# FlashPanelV6_0.net
KiCad netlist of a schematic drawn in EAGLE
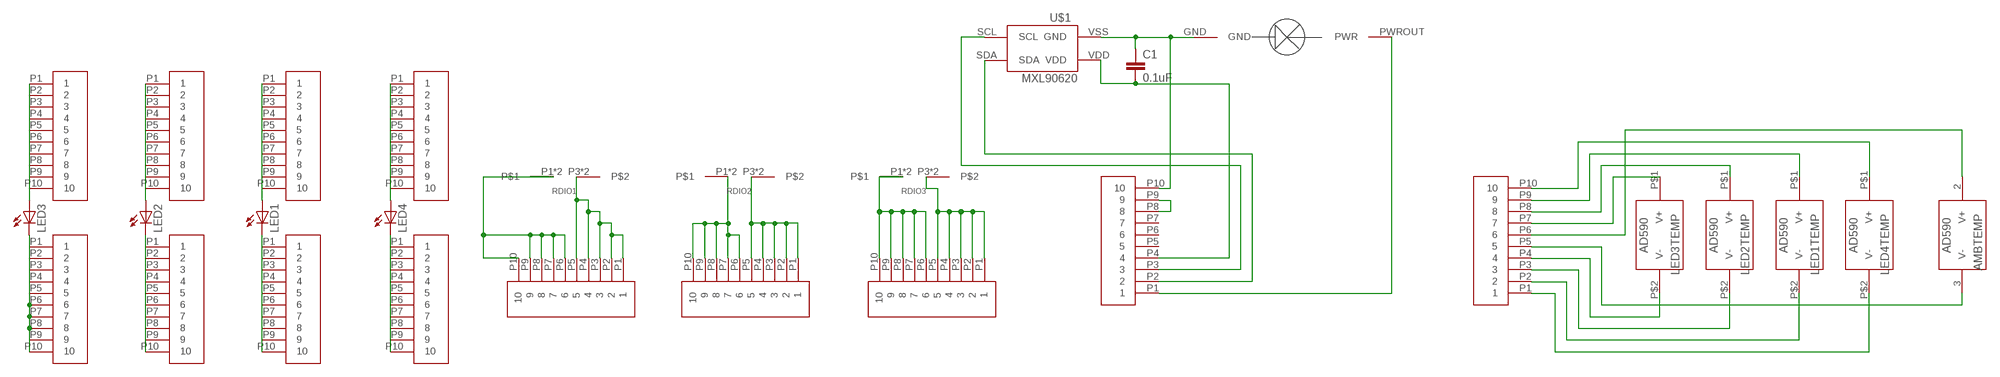
[diagram p0: schematic, sheet 1]

(export (version "E")
  (design (tool "Eeschema 10.0.6"))
  (components
    (comp (ref "AMBTEMP")
      (value "AD590")
      (footprint "eagle-import:8SOIC")
      (libsource (lib "eagle-import") (part "AD590-SOIC-8"))
    )
    (comp (ref "ANTDEP1M")
      (value "10PINMALE")
      (footprint "eagle-import:10PINMALE")
      (libsource (lib "eagle-import") (part "10PINMALE"))
    )
    (comp (ref "ANTDEP2M")
      (value "10PINMALE")
      (footprint "eagle-import:10PINMALE")
      (libsource (lib "eagle-import") (part "10PINMALE"))
    )
    (comp (ref "ANTDEP3M")
      (value "10PINMALE")
      (footprint "eagle-import:10PINMALE")
      (libsource (lib "eagle-import") (part "10PINMALE"))
    )
    (comp (ref "C1")
      (value "0.1uF")
      (footprint "eagle-import:0805")
      (libsource (lib "eagle-import") (part "CAP0805"))
    )
    (comp (ref "CONN13M")
      (value "10PINMALE")
      (footprint "eagle-import:10PINMALE")
      (libsource (lib "eagle-import") (part "10PINMALE"))
    )
    (comp (ref "LED1")
      (value "CXM27")
      (footprint "eagle-import:CXM27")
      (libsource (lib "eagle-import") (part "CXM27"))
    )
    (comp (ref "LED1+M")
      (value "10PINMALE")
      (footprint "eagle-import:10PINMALE")
      (libsource (lib "eagle-import") (part "10PINMALE"))
    )
    (comp (ref "LED1-M")
      (value "10PINMALE")
      (footprint "eagle-import:10PINMALE")
      (libsource (lib "eagle-import") (part "10PINMALE"))
    )
    (comp (ref "LED1TEMP")
      (value "AD590-TH")
      (footprint "eagle-import:AD590TH")
      (libsource (lib "eagle-import") (part "AD590-TH"))
    )
    (comp (ref "LED2")
      (value "CXM27")
      (footprint "eagle-import:CXM27")
      (libsource (lib "eagle-import") (part "CXM27"))
    )
    (comp (ref "LED2+M")
      (value "10PINMALE")
      (footprint "eagle-import:10PINMALE")
      (libsource (lib "eagle-import") (part "10PINMALE"))
    )
    (comp (ref "LED2-M")
      (value "10PINMALE")
      (footprint "eagle-import:10PINMALE")
      (libsource (lib "eagle-import") (part "10PINMALE"))
    )
    (comp (ref "LED2TEMP")
      (value "AD590-TH")
      (footprint "eagle-import:AD590TH")
      (libsource (lib "eagle-import") (part "AD590-TH"))
    )
    (comp (ref "LED3")
      (value "CXM27")
      (footprint "eagle-import:CXM27")
      (libsource (lib "eagle-import") (part "CXM27"))
    )
    (comp (ref "LED3+M")
      (value "10PINMALE")
      (footprint "eagle-import:10PINMALE")
      (libsource (lib "eagle-import") (part "10PINMALE"))
    )
    (comp (ref "LED3-M")
      (value "10PINMALE")
      (footprint "eagle-import:10PINMALE")
      (libsource (lib "eagle-import") (part "10PINMALE"))
    )
    (comp (ref "LED3TEMP")
      (value "AD590-TH")
      (footprint "eagle-import:AD590TH")
      (libsource (lib "eagle-import") (part "AD590-TH"))
    )
    (comp (ref "LED4")
      (value "CXM27")
      (footprint "eagle-import:CXM27")
      (libsource (lib "eagle-import") (part "CXM27"))
    )
    (comp (ref "LED4+M")
      (value "10PINMALE")
      (footprint "eagle-import:10PINMALE")
      (libsource (lib "eagle-import") (part "10PINMALE"))
    )
    (comp (ref "LED4-M")
      (value "10PINMALE")
      (footprint "eagle-import:10PINMALE")
      (libsource (lib "eagle-import") (part "10PINMALE"))
    )
    (comp (ref "LED4TEMP")
      (value "AD590-TH")
      (footprint "eagle-import:AD590TH")
      (libsource (lib "eagle-import") (part "AD590-TH"))
    )
    (comp (ref "RDIO1")
      (value "RDIO")
      (footprint "eagle-import:RDIO_DPLY")
      (libsource (lib "eagle-import") (part "RDIO"))
    )
    (comp (ref "RDIO2")
      (value "RDIO")
      (footprint "eagle-import:RDIO_DPLY")
      (libsource (lib "eagle-import") (part "RDIO"))
    )
    (comp (ref "RDIO3")
      (value "RDIO")
      (footprint "eagle-import:RDIO_DPLY")
      (libsource (lib "eagle-import") (part "RDIO"))
    )
    (comp (ref "TEMPCONNM")
      (value "10PINMALE")
      (footprint "eagle-import:10PINMALE")
      (libsource (lib "eagle-import") (part "10PINMALE"))
    )
    (comp (ref "U$1")
      (value "MXL90620")
      (footprint "eagle-import:MXL90620")
      (libsource (lib "eagle-import") (part "MXL90620"))
    )
    (comp (ref "U$2")
      (value "PHOTODETECTBOTTOM")
      (footprint "eagle-import:PHOTODETECTBOTTOM")
      (libsource (lib "eagle-import") (part "PHOTODETECTBOTTOM"))
    )
  )
  (nets
    (net (code "1") (name "Net-(AMBTEMP-V+)") (class "Default")
      (node (ref "AMBTEMP") (pin "2") (pinfunction "V+_2") (pintype "bidirectional"))
      (node (ref "TEMPCONNM") (pin "P6") (pinfunction "6_P6") (pintype "bidirectional"))
    )
    (net (code "2") (name "Net-(AMBTEMP-V-)") (class "Default")
      (node (ref "AMBTEMP") (pin "3") (pinfunction "V-_3") (pintype "bidirectional"))
      (node (ref "TEMPCONNM") (pin "P5") (pinfunction "5_P5") (pintype "bidirectional"))
    )
    (net (code "3") (name "Net-(ANTDEP1M-1)") (class "Default")
      (node (ref "ANTDEP1M") (pin "P1") (pinfunction "1_P1") (pintype "bidirectional"))
      (node (ref "ANTDEP1M") (pin "P2") (pinfunction "2_P2") (pintype "bidirectional"))
      (node (ref "ANTDEP1M") (pin "P3") (pinfunction "3_P3") (pintype "bidirectional"))
      (node (ref "ANTDEP1M") (pin "P4") (pinfunction "4_P4") (pintype "bidirectional"))
      (node (ref "ANTDEP1M") (pin "P5") (pinfunction "5_P5") (pintype "bidirectional"))
      (node (ref "RDIO1") (pin "P3") (pinfunction "P$2_P3") (pintype "bidirectional"))
      (node (ref "RDIO1") (pin "P4") (pinfunction "P$2_P4") (pintype "bidirectional"))
    )
    (net (code "4") (name "Net-(ANTDEP1M-10)") (class "Default")
      (node (ref "ANTDEP1M") (pin "P10") (pinfunction "10_P10") (pintype "bidirectional"))
      (node (ref "ANTDEP1M") (pin "P6") (pinfunction "6_P6") (pintype "bidirectional"))
      (node (ref "ANTDEP1M") (pin "P7") (pinfunction "7_P7") (pintype "bidirectional"))
      (node (ref "ANTDEP1M") (pin "P8") (pinfunction "8_P8") (pintype "bidirectional"))
      (node (ref "ANTDEP1M") (pin "P9") (pinfunction "9_P9") (pintype "bidirectional"))
      (node (ref "RDIO1") (pin "P1") (pinfunction "P$1_P1") (pintype "bidirectional"))
      (node (ref "RDIO1") (pin "P2") (pinfunction "P$1_P2") (pintype "bidirectional"))
    )
    (net (code "5") (name "Net-(ANTDEP2M-1)") (class "Default")
      (node (ref "ANTDEP2M") (pin "P1") (pinfunction "1_P1") (pintype "bidirectional"))
      (node (ref "ANTDEP2M") (pin "P2") (pinfunction "2_P2") (pintype "bidirectional"))
      (node (ref "ANTDEP2M") (pin "P3") (pinfunction "3_P3") (pintype "bidirectional"))
      (node (ref "ANTDEP2M") (pin "P4") (pinfunction "4_P4") (pintype "bidirectional"))
      (node (ref "ANTDEP2M") (pin "P5") (pinfunction "5_P5") (pintype "bidirectional"))
      (node (ref "RDIO2") (pin "P3") (pinfunction "P$2_P3") (pintype "bidirectional"))
      (node (ref "RDIO2") (pin "P4") (pinfunction "P$2_P4") (pintype "bidirectional"))
    )
    (net (code "6") (name "Net-(ANTDEP2M-10)") (class "Default")
      (node (ref "ANTDEP2M") (pin "P10") (pinfunction "10_P10") (pintype "bidirectional"))
      (node (ref "ANTDEP2M") (pin "P6") (pinfunction "6_P6") (pintype "bidirectional"))
      (node (ref "ANTDEP2M") (pin "P7") (pinfunction "7_P7") (pintype "bidirectional"))
      (node (ref "ANTDEP2M") (pin "P8") (pinfunction "8_P8") (pintype "bidirectional"))
      (node (ref "ANTDEP2M") (pin "P9") (pinfunction "9_P9") (pintype "bidirectional"))
      (node (ref "RDIO2") (pin "P1") (pinfunction "P$1_P1") (pintype "bidirectional"))
      (node (ref "RDIO2") (pin "P2") (pinfunction "P$1_P2") (pintype "bidirectional"))
    )
    (net (code "7") (name "Net-(ANTDEP3M-1)") (class "Default")
      (node (ref "ANTDEP3M") (pin "P1") (pinfunction "1_P1") (pintype "bidirectional"))
      (node (ref "ANTDEP3M") (pin "P2") (pinfunction "2_P2") (pintype "bidirectional"))
      (node (ref "ANTDEP3M") (pin "P3") (pinfunction "3_P3") (pintype "bidirectional"))
      (node (ref "ANTDEP3M") (pin "P4") (pinfunction "4_P4") (pintype "bidirectional"))
      (node (ref "ANTDEP3M") (pin "P5") (pinfunction "5_P5") (pintype "bidirectional"))
      (node (ref "RDIO3") (pin "P3") (pinfunction "P$2_P3") (pintype "bidirectional"))
      (node (ref "RDIO3") (pin "P4") (pinfunction "P$2_P4") (pintype "bidirectional"))
    )
    (net (code "8") (name "Net-(ANTDEP3M-10)") (class "Default")
      (node (ref "ANTDEP3M") (pin "P10") (pinfunction "10_P10") (pintype "bidirectional"))
      (node (ref "ANTDEP3M") (pin "P6") (pinfunction "6_P6") (pintype "bidirectional"))
      (node (ref "ANTDEP3M") (pin "P7") (pinfunction "7_P7") (pintype "bidirectional"))
      (node (ref "ANTDEP3M") (pin "P8") (pinfunction "8_P8") (pintype "bidirectional"))
      (node (ref "ANTDEP3M") (pin "P9") (pinfunction "9_P9") (pintype "bidirectional"))
      (node (ref "RDIO3") (pin "P1") (pinfunction "P$1_P1") (pintype "bidirectional"))
      (node (ref "RDIO3") (pin "P2") (pinfunction "P$1_P2") (pintype "bidirectional"))
    )
    (net (code "9") (name "Net-(CONN13M-1)") (class "Default")
      (node (ref "CONN13M") (pin "P1") (pinfunction "1_P1") (pintype "bidirectional"))
      (node (ref "U$2") (pin "PWROUT") (pinfunction "PWR_PWROUT") (pintype "bidirectional"))
    )
    (net (code "10") (name "Net-(CONN13M-2)") (class "Default")
      (node (ref "CONN13M") (pin "P2") (pinfunction "2_P2") (pintype "bidirectional"))
      (node (ref "U$1") (pin "SDA") (pinfunction "SDA_SDA") (pintype "bidirectional"))
    )
    (net (code "11") (name "Net-(CONN13M-3)") (class "Default")
      (node (ref "CONN13M") (pin "P3") (pinfunction "3_P3") (pintype "bidirectional"))
      (node (ref "U$1") (pin "SCL") (pinfunction "SCL_SCL") (pintype "bidirectional"))
    )
    (net (code "12") (name "Net-(CONN13M-4)") (class "Default")
      (node (ref "C1") (pin "2") (pinfunction "2_2") (pintype "passive"))
      (node (ref "CONN13M") (pin "P4") (pinfunction "4_P4") (pintype "bidirectional"))
      (node (ref "U$1") (pin "VDD") (pinfunction "VDD_VDD") (pintype "bidirectional"))
    )
    (net (code "13") (name "Net-(CONN13M-8)") (class "Default")
      (node (ref "CONN13M") (pin "P8") (pinfunction "8_P8") (pintype "bidirectional"))
      (node (ref "CONN13M") (pin "P9") (pinfunction "9_P9") (pintype "bidirectional"))
    )
    (net (code "14") (name "Net-(CONN13M-10)") (class "Default")
      (node (ref "C1") (pin "1") (pinfunction "1_1") (pintype "passive"))
      (node (ref "CONN13M") (pin "P10") (pinfunction "10_P10") (pintype "bidirectional"))
      (node (ref "U$1") (pin "VSS") (pinfunction "GND_VSS") (pintype "bidirectional"))
      (node (ref "U$2") (pin "GND") (pinfunction "GND_GND") (pintype "bidirectional"))
    )
    (net (code "15") (name "Net-(LED1+M-1)") (class "Default")
      (node (ref "LED1") (pin "CATHODE") (pinfunction "C_CATHODE") (pintype "passive"))
      (node (ref "LED1+M") (pin "P1") (pinfunction "1_P1") (pintype "bidirectional"))
      (node (ref "LED1+M") (pin "P10") (pinfunction "10_P10") (pintype "bidirectional"))
      (node (ref "LED1+M") (pin "P2") (pinfunction "2_P2") (pintype "bidirectional"))
      (node (ref "LED1+M") (pin "P3") (pinfunction "3_P3") (pintype "bidirectional"))
      (node (ref "LED1+M") (pin "P4") (pinfunction "4_P4") (pintype "bidirectional"))
      (node (ref "LED1+M") (pin "P5") (pinfunction "5_P5") (pintype "bidirectional"))
      (node (ref "LED1+M") (pin "P6") (pinfunction "6_P6") (pintype "bidirectional"))
      (node (ref "LED1+M") (pin "P7") (pinfunction "7_P7") (pintype "bidirectional"))
      (node (ref "LED1+M") (pin "P8") (pinfunction "8_P8") (pintype "bidirectional"))
      (node (ref "LED1+M") (pin "P9") (pinfunction "9_P9") (pintype "bidirectional"))
    )
    (net (code "16") (name "Net-(LED1-A)") (class "Default")
      (node (ref "LED1") (pin "ANODE") (pinfunction "A_ANODE") (pintype "passive"))
      (node (ref "LED1-M") (pin "P1") (pinfunction "1_P1") (pintype "bidirectional"))
      (node (ref "LED1-M") (pin "P10") (pinfunction "10_P10") (pintype "bidirectional"))
      (node (ref "LED1-M") (pin "P2") (pinfunction "2_P2") (pintype "bidirectional"))
      (node (ref "LED1-M") (pin "P3") (pinfunction "3_P3") (pintype "bidirectional"))
      (node (ref "LED1-M") (pin "P4") (pinfunction "4_P4") (pintype "bidirectional"))
      (node (ref "LED1-M") (pin "P5") (pinfunction "5_P5") (pintype "bidirectional"))
      (node (ref "LED1-M") (pin "P6") (pinfunction "6_P6") (pintype "bidirectional"))
      (node (ref "LED1-M") (pin "P7") (pinfunction "7_P7") (pintype "bidirectional"))
      (node (ref "LED1-M") (pin "P8") (pinfunction "8_P8") (pintype "bidirectional"))
      (node (ref "LED1-M") (pin "P9") (pinfunction "9_P9") (pintype "bidirectional"))
    )
    (net (code "17") (name "Net-(LED1TEMP-V+)") (class "Default")
      (node (ref "LED1TEMP") (pin "P$1") (pinfunction "V+_P$1") (pintype "bidirectional"))
      (node (ref "TEMPCONNM") (pin "P9") (pinfunction "9_P9") (pintype "bidirectional"))
    )
    (net (code "18") (name "Net-(LED1TEMP-V-)") (class "Default")
      (node (ref "LED1TEMP") (pin "P$2") (pinfunction "V-_P$2") (pintype "bidirectional"))
      (node (ref "TEMPCONNM") (pin "P2") (pinfunction "2_P2") (pintype "bidirectional"))
    )
    (net (code "19") (name "Net-(LED2+M-1)") (class "Default")
      (node (ref "LED2") (pin "CATHODE") (pinfunction "C_CATHODE") (pintype "passive"))
      (node (ref "LED2+M") (pin "P1") (pinfunction "1_P1") (pintype "bidirectional"))
      (node (ref "LED2+M") (pin "P10") (pinfunction "10_P10") (pintype "bidirectional"))
      (node (ref "LED2+M") (pin "P2") (pinfunction "2_P2") (pintype "bidirectional"))
      (node (ref "LED2+M") (pin "P3") (pinfunction "3_P3") (pintype "bidirectional"))
      (node (ref "LED2+M") (pin "P4") (pinfunction "4_P4") (pintype "bidirectional"))
      (node (ref "LED2+M") (pin "P5") (pinfunction "5_P5") (pintype "bidirectional"))
      (node (ref "LED2+M") (pin "P6") (pinfunction "6_P6") (pintype "bidirectional"))
      (node (ref "LED2+M") (pin "P7") (pinfunction "7_P7") (pintype "bidirectional"))
      (node (ref "LED2+M") (pin "P8") (pinfunction "8_P8") (pintype "bidirectional"))
      (node (ref "LED2+M") (pin "P9") (pinfunction "9_P9") (pintype "bidirectional"))
    )
    (net (code "20") (name "Net-(LED2-A)") (class "Default")
      (node (ref "LED2") (pin "ANODE") (pinfunction "A_ANODE") (pintype "passive"))
      (node (ref "LED2-M") (pin "P1") (pinfunction "1_P1") (pintype "bidirectional"))
      (node (ref "LED2-M") (pin "P10") (pinfunction "10_P10") (pintype "bidirectional"))
      (node (ref "LED2-M") (pin "P2") (pinfunction "2_P2") (pintype "bidirectional"))
      (node (ref "LED2-M") (pin "P3") (pinfunction "3_P3") (pintype "bidirectional"))
      (node (ref "LED2-M") (pin "P4") (pinfunction "4_P4") (pintype "bidirectional"))
      (node (ref "LED2-M") (pin "P5") (pinfunction "5_P5") (pintype "bidirectional"))
      (node (ref "LED2-M") (pin "P6") (pinfunction "6_P6") (pintype "bidirectional"))
      (node (ref "LED2-M") (pin "P7") (pinfunction "7_P7") (pintype "bidirectional"))
      (node (ref "LED2-M") (pin "P8") (pinfunction "8_P8") (pintype "bidirectional"))
      (node (ref "LED2-M") (pin "P9") (pinfunction "9_P9") (pintype "bidirectional"))
    )
    (net (code "21") (name "Net-(LED2TEMP-V+)") (class "Default")
      (node (ref "LED2TEMP") (pin "P$1") (pinfunction "V+_P$1") (pintype "bidirectional"))
      (node (ref "TEMPCONNM") (pin "P8") (pinfunction "8_P8") (pintype "bidirectional"))
    )
    (net (code "22") (name "Net-(LED2TEMP-V-)") (class "Default")
      (node (ref "LED2TEMP") (pin "P$2") (pinfunction "V-_P$2") (pintype "bidirectional"))
      (node (ref "TEMPCONNM") (pin "P3") (pinfunction "3_P3") (pintype "bidirectional"))
    )
    (net (code "23") (name "Net-(LED3+M-1)") (class "Default")
      (node (ref "LED3") (pin "ANODE") (pinfunction "A_ANODE") (pintype "passive"))
      (node (ref "LED3+M") (pin "P1") (pinfunction "1_P1") (pintype "bidirectional"))
      (node (ref "LED3+M") (pin "P10") (pinfunction "10_P10") (pintype "bidirectional"))
      (node (ref "LED3+M") (pin "P2") (pinfunction "2_P2") (pintype "bidirectional"))
      (node (ref "LED3+M") (pin "P3") (pinfunction "3_P3") (pintype "bidirectional"))
      (node (ref "LED3+M") (pin "P4") (pinfunction "4_P4") (pintype "bidirectional"))
      (node (ref "LED3+M") (pin "P5") (pinfunction "5_P5") (pintype "bidirectional"))
      (node (ref "LED3+M") (pin "P6") (pinfunction "6_P6") (pintype "bidirectional"))
      (node (ref "LED3+M") (pin "P7") (pinfunction "7_P7") (pintype "bidirectional"))
      (node (ref "LED3+M") (pin "P8") (pinfunction "8_P8") (pintype "bidirectional"))
      (node (ref "LED3+M") (pin "P9") (pinfunction "9_P9") (pintype "bidirectional"))
    )
    (net (code "24") (name "Net-(LED3-C)") (class "Default")
      (node (ref "LED3") (pin "CATHODE") (pinfunction "C_CATHODE") (pintype "passive"))
      (node (ref "LED3-M") (pin "P1") (pinfunction "1_P1") (pintype "bidirectional"))
      (node (ref "LED3-M") (pin "P10") (pinfunction "10_P10") (pintype "bidirectional"))
      (node (ref "LED3-M") (pin "P2") (pinfunction "2_P2") (pintype "bidirectional"))
      (node (ref "LED3-M") (pin "P3") (pinfunction "3_P3") (pintype "bidirectional"))
      (node (ref "LED3-M") (pin "P4") (pinfunction "4_P4") (pintype "bidirectional"))
      (node (ref "LED3-M") (pin "P5") (pinfunction "5_P5") (pintype "bidirectional"))
      (node (ref "LED3-M") (pin "P6") (pinfunction "6_P6") (pintype "bidirectional"))
      (node (ref "LED3-M") (pin "P7") (pinfunction "7_P7") (pintype "bidirectional"))
      (node (ref "LED3-M") (pin "P8") (pinfunction "8_P8") (pintype "bidirectional"))
      (node (ref "LED3-M") (pin "P9") (pinfunction "9_P9") (pintype "bidirectional"))
    )
    (net (code "25") (name "Net-(LED3TEMP-V+)") (class "Default")
      (node (ref "LED3TEMP") (pin "P$1") (pinfunction "V+_P$1") (pintype "bidirectional"))
      (node (ref "TEMPCONNM") (pin "P7") (pinfunction "7_P7") (pintype "bidirectional"))
    )
    (net (code "26") (name "Net-(LED3TEMP-V-)") (class "Default")
      (node (ref "LED3TEMP") (pin "P$2") (pinfunction "V-_P$2") (pintype "bidirectional"))
      (node (ref "TEMPCONNM") (pin "P4") (pinfunction "4_P4") (pintype "bidirectional"))
    )
    (net (code "27") (name "Net-(LED4+M-1)") (class "Default")
      (node (ref "LED4") (pin "ANODE") (pinfunction "A_ANODE") (pintype "passive"))
      (node (ref "LED4+M") (pin "P1") (pinfunction "1_P1") (pintype "bidirectional"))
      (node (ref "LED4+M") (pin "P10") (pinfunction "10_P10") (pintype "bidirectional"))
      (node (ref "LED4+M") (pin "P2") (pinfunction "2_P2") (pintype "bidirectional"))
      (node (ref "LED4+M") (pin "P3") (pinfunction "3_P3") (pintype "bidirectional"))
      (node (ref "LED4+M") (pin "P4") (pinfunction "4_P4") (pintype "bidirectional"))
      (node (ref "LED4+M") (pin "P5") (pinfunction "5_P5") (pintype "bidirectional"))
      (node (ref "LED4+M") (pin "P6") (pinfunction "6_P6") (pintype "bidirectional"))
      (node (ref "LED4+M") (pin "P7") (pinfunction "7_P7") (pintype "bidirectional"))
      (node (ref "LED4+M") (pin "P8") (pinfunction "8_P8") (pintype "bidirectional"))
      (node (ref "LED4+M") (pin "P9") (pinfunction "9_P9") (pintype "bidirectional"))
    )
    (net (code "28") (name "Net-(LED4-C)") (class "Default")
      (node (ref "LED4") (pin "CATHODE") (pinfunction "C_CATHODE") (pintype "passive"))
      (node (ref "LED4-M") (pin "P1") (pinfunction "1_P1") (pintype "bidirectional"))
      (node (ref "LED4-M") (pin "P10") (pinfunction "10_P10") (pintype "bidirectional"))
      (node (ref "LED4-M") (pin "P2") (pinfunction "2_P2") (pintype "bidirectional"))
      (node (ref "LED4-M") (pin "P3") (pinfunction "3_P3") (pintype "bidirectional"))
      (node (ref "LED4-M") (pin "P4") (pinfunction "4_P4") (pintype "bidirectional"))
      (node (ref "LED4-M") (pin "P5") (pinfunction "5_P5") (pintype "bidirectional"))
      (node (ref "LED4-M") (pin "P6") (pinfunction "6_P6") (pintype "bidirectional"))
      (node (ref "LED4-M") (pin "P7") (pinfunction "7_P7") (pintype "bidirectional"))
      (node (ref "LED4-M") (pin "P8") (pinfunction "8_P8") (pintype "bidirectional"))
      (node (ref "LED4-M") (pin "P9") (pinfunction "9_P9") (pintype "bidirectional"))
    )
    (net (code "29") (name "Net-(LED4TEMP-V+)") (class "Default")
      (node (ref "LED4TEMP") (pin "P$1") (pinfunction "V+_P$1") (pintype "bidirectional"))
      (node (ref "TEMPCONNM") (pin "P10") (pinfunction "10_P10") (pintype "bidirectional"))
    )
    (net (code "30") (name "Net-(LED4TEMP-V-)") (class "Default")
      (node (ref "LED4TEMP") (pin "P$2") (pinfunction "V-_P$2") (pintype "bidirectional"))
      (node (ref "TEMPCONNM") (pin "P1") (pinfunction "1_P1") (pintype "bidirectional"))
    )
    (net (code "31") (name "unconnected-(CONN13M-5-PadP5)") (class "Default")
      (node (ref "CONN13M") (pin "P5") (pinfunction "5_P5") (pintype "bidirectional"))
    )
    (net (code "32") (name "unconnected-(CONN13M-6-PadP6)") (class "Default")
      (node (ref "CONN13M") (pin "P6") (pinfunction "6_P6") (pintype "bidirectional"))
    )
    (net (code "33") (name "unconnected-(CONN13M-7-PadP7)") (class "Default")
      (node (ref "CONN13M") (pin "P7") (pinfunction "7_P7") (pintype "bidirectional"))
    )
  )
)
